# FEED_TIMER_DP_7.net
KiCad netlist of a schematic drawn in Altium Designer
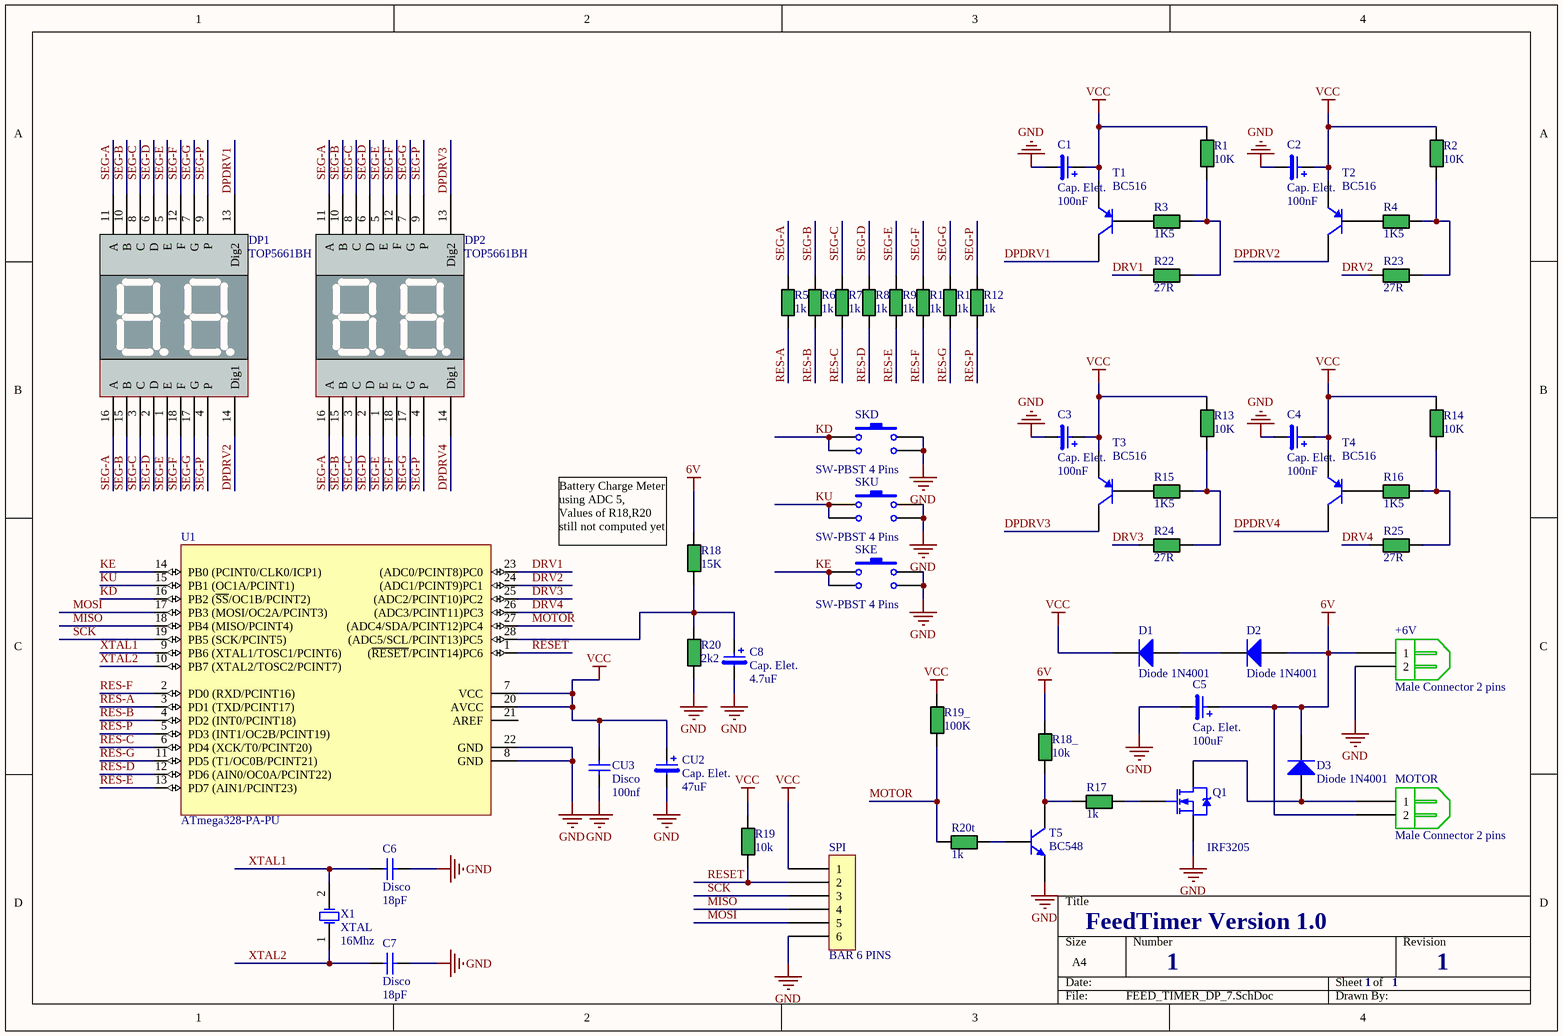
[diagram p0: FEED_TIMER_DP_7.SchDoc]

(export (version "E")
  (design (tool "Eeschema 10.0.6"))
  (components
    (comp (ref "+6V")
      (value "Male Connector 2 pins")
      (footprint "BR102A")
      (libsource (lib "NEPERMATH") (part "Male Con 2 Pin"))
    )
    (comp (ref "C1")
      (value "Cap. Elet.")
      (footprint "CAP ELE RAD 11mm H")
      (description "Capacitor Radial Eletrolitico")
      (fields (field (name "ALTIUM_VALUE") "100nF"))
      (libsource (lib "NEPERMATH") (part "CAP_RADIAL_ELETROLITICO"))
    )
    (comp (ref "C2")
      (value "Cap. Elet.")
      (footprint "CAP ELE RAD 11mm H")
      (description "Capacitor Radial Eletrolitico")
      (fields (field (name "ALTIUM_VALUE") "100nF"))
      (libsource (lib "NEPERMATH") (part "CAP_RADIAL_ELETROLITICO"))
    )
    (comp (ref "C3")
      (value "Cap. Elet.")
      (footprint "CAP ELE RAD 11mm H")
      (description "Capacitor Radial Eletrolitico")
      (fields (field (name "ALTIUM_VALUE") "100nF"))
      (libsource (lib "NEPERMATH") (part "CAP_RADIAL_ELETROLITICO"))
    )
    (comp (ref "C4")
      (value "Cap. Elet.")
      (footprint "CAP ELE RAD 11mm H")
      (description "Capacitor Radial Eletrolitico")
      (fields (field (name "ALTIUM_VALUE") "100nF"))
      (libsource (lib "NEPERMATH") (part "CAP_RADIAL_ELETROLITICO"))
    )
    (comp (ref "C5")
      (value "Cap. Elet.")
      (footprint "CAP_RADIAL_2_10_16")
      (description "Capacitor Radial Eletrolitico")
      (fields (field (name "ALTIUM_VALUE") "100uF"))
      (libsource (lib "NEPERMATH") (part "CAP_RADIAL_ELETROLITICO"))
    )
    (comp (ref "C6")
      (value "Disco")
      (footprint "CAP CER DISK 3MM")
      (description "SMD Capacitor 1210 size")
      (fields (field (name "ALTIUM_VALUE") "18pF"))
      (libsource (lib "NEPERMATH") (part "CAP_DISCO"))
    )
    (comp (ref "C7")
      (value "Disco")
      (footprint "CAP CER DISK 3MM")
      (description "SMD Capacitor 1210 size")
      (fields (field (name "ALTIUM_VALUE") "18pF"))
      (libsource (lib "NEPERMATH") (part "CAP_DISCO"))
    )
    (comp (ref "C8")
      (value "Cap. Elet.")
      (footprint "CAP ELE RAD 11mm H")
      (description "Capacitor Radial Eletrolitico")
      (fields (field (name "ALTIUM_VALUE") "4.7uF"))
      (libsource (lib "NEPERMATH") (part "CAP_RADIAL_ELETROLITICO"))
    )
    (comp (ref "CU2")
      (value "Cap. Elet.")
      (footprint "CAP ELE RAD 11mm H")
      (description "Capacitor Radial Eletrolitico")
      (fields (field (name "ALTIUM_VALUE") "47uF"))
      (libsource (lib "NEPERMATH") (part "CAP_RADIAL_ELETROLITICO"))
    )
    (comp (ref "CU3")
      (value "Disco")
      (footprint "CAP CER DISK 5MM")
      (description "SMD Capacitor 1210 size")
      (fields (field (name "ALTIUM_VALUE") "100nf"))
      (libsource (lib "NEPERMATH") (part "CAP_DISCO"))
    )
    (comp (ref "D1")
      (value "Diode 1N4001")
      (footprint "DO-41")
      (description "1 Amp General Purpose Rectifier")
      (fields (field (name "PUBLISHER") "Altium Limited"))
      (libsource (lib "NEPERMATH") (part "Diode 1N4001"))
    )
    (comp (ref "D2")
      (value "Diode 1N4001")
      (footprint "DO-41")
      (description "1 Amp General Purpose Rectifier")
      (fields (field (name "PUBLISHER") "Altium Limited"))
      (libsource (lib "NEPERMATH") (part "Diode 1N4001"))
    )
    (comp (ref "D3")
      (value "Diode 1N4001")
      (footprint "DO-41")
      (description "1 Amp General Purpose Rectifier")
      (fields (field (name "PUBLISHER") "Altium Limited"))
      (libsource (lib "NEPERMATH") (part "Diode 1N4001"))
    )
    (comp (ref "DP1")
      (value "TOP5661BH")
      (footprint "DISPLAY TOP_5261BH")
      (description "7 seg display")
      (libsource (lib "NEPERMATH") (part "DISPLAY TOP_5261BH"))
    )
    (comp (ref "DP2")
      (value "TOP5661BH")
      (footprint "DISPLAY TOP_5261BH")
      (description "7 seg display")
      (libsource (lib "NEPERMATH") (part "DISPLAY TOP_5261BH"))
    )
    (comp (ref "MOTOR")
      (value "Male Connector 2 pins")
      (footprint "BR102A")
      (libsource (lib "NEPERMATH") (part "Male Con 2 Pin"))
    )
    (comp (ref "Q1")
      (value "IRF3205")
      (footprint "KC03 - Deitado")
      (description "HEXFET Power MOSFET")
      (libsource (lib "NEPERMATH") (part "T-HEXFET N"))
    )
    (comp (ref "R1")
      (value "10K")
      (footprint "RES 300 CR25")
      (description "Generic Resistor")
      (fields (field (name "Comment") "Resistor Generic"))
      (libsource (lib "") (part "Resistor Generic_1"))
    )
    (comp (ref "R2")
      (value "10K")
      (footprint "RES 300 CR25")
      (description "Generic Resistor")
      (fields (field (name "Comment") "Resistor Generic"))
      (libsource (lib "") (part "Resistor Generic_1"))
    )
    (comp (ref "R3")
      (value "1K5")
      (footprint "RES 300 CR25")
      (description "Generic Resistor")
      (fields (field (name "Comment") "Resistor Generic"))
      (libsource (lib "NEPERMATH") (part "Resistor Generic"))
    )
    (comp (ref "R4")
      (value "1K5")
      (footprint "RES 300 CR25")
      (description "Generic Resistor")
      (fields (field (name "Comment") "Resistor Generic"))
      (libsource (lib "NEPERMATH") (part "Resistor Generic"))
    )
    (comp (ref "R5")
      (value "1k")
      (footprint "RES 300 CR25")
      (description "Generic Resistor")
      (fields (field (name "Comment") "Resistor Generic"))
      (libsource (lib "") (part "Resistor Generic_2"))
    )
    (comp (ref "R6")
      (value "1k")
      (footprint "RES 300 CR25")
      (description "Generic Resistor")
      (fields (field (name "Comment") "Resistor Generic"))
      (libsource (lib "") (part "Resistor Generic_2"))
    )
    (comp (ref "R7")
      (value "1k")
      (footprint "RES 300 CR25")
      (description "Generic Resistor")
      (fields (field (name "Comment") "Resistor Generic"))
      (libsource (lib "") (part "Resistor Generic_2"))
    )
    (comp (ref "R8")
      (value "1k")
      (footprint "RES 300 CR25")
      (description "Generic Resistor")
      (fields (field (name "Comment") "Resistor Generic"))
      (libsource (lib "") (part "Resistor Generic_2"))
    )
    (comp (ref "R9")
      (value "1k")
      (footprint "RES 300 CR25")
      (description "Generic Resistor")
      (fields (field (name "Comment") "Resistor Generic"))
      (libsource (lib "") (part "Resistor Generic_2"))
    )
    (comp (ref "R10")
      (value "1k")
      (footprint "RES 300 CR25")
      (description "Generic Resistor")
      (fields (field (name "Comment") "Resistor Generic"))
      (libsource (lib "") (part "Resistor Generic_2"))
    )
    (comp (ref "R11")
      (value "1k")
      (footprint "RES 300 CR25")
      (description "Generic Resistor")
      (fields (field (name "Comment") "Resistor Generic"))
      (libsource (lib "") (part "Resistor Generic_2"))
    )
    (comp (ref "R12")
      (value "1k")
      (footprint "RES 300 CR25")
      (description "Generic Resistor")
      (fields (field (name "Comment") "Resistor Generic"))
      (libsource (lib "") (part "Resistor Generic_2"))
    )
    (comp (ref "R13")
      (value "10K")
      (footprint "RES 300 CR25")
      (description "Generic Resistor")
      (fields (field (name "Comment") "Resistor Generic"))
      (libsource (lib "") (part "Resistor Generic_1"))
    )
    (comp (ref "R14")
      (value "10K")
      (footprint "RES 300 CR25")
      (description "Generic Resistor")
      (fields (field (name "Comment") "Resistor Generic"))
      (libsource (lib "") (part "Resistor Generic_1"))
    )
    (comp (ref "R15")
      (value "1K5")
      (footprint "RES 300 CR25")
      (description "Generic Resistor")
      (fields (field (name "Comment") "Resistor Generic"))
      (libsource (lib "NEPERMATH") (part "Resistor Generic"))
    )
    (comp (ref "R16")
      (value "1K5")
      (footprint "RES 300 CR25")
      (description "Generic Resistor")
      (fields (field (name "Comment") "Resistor Generic"))
      (libsource (lib "NEPERMATH") (part "Resistor Generic"))
    )
    (comp (ref "R17")
      (value "1k")
      (footprint "RES 300 CR25")
      (description "Generic Resistor")
      (fields (field (name "Comment") "Resistor Generic"))
      (libsource (lib "NEPERMATH") (part "Resistor Generic"))
    )
    (comp (ref "R18")
      (value "15K")
      (footprint "RES 300 CR25")
      (description "Generic Resistor")
      (fields (field (name "Comment") "Resistor Generic"))
      (libsource (lib "") (part "Resistor Generic_1"))
    )
    (comp (ref "R18_")
      (value "10k")
      (footprint "RES 300 CR25")
      (description "Generic Resistor")
      (fields (field (name "Comment") "Resistor Generic"))
      (libsource (lib "") (part "Resistor Generic_1"))
    )
    (comp (ref "R19")
      (value "10k")
      (footprint "RES 300 CR25")
      (description "Generic Resistor")
      (fields (field (name "Comment") "Resistor Generic"))
      (libsource (lib "") (part "Resistor Generic_1"))
    )
    (comp (ref "R19_")
      (value "100K")
      (footprint "RES 300 CR25")
      (description "Generic Resistor")
      (fields (field (name "Comment") "Resistor Generic"))
      (libsource (lib "") (part "Resistor Generic_1"))
    )
    (comp (ref "R20")
      (value "2k2")
      (footprint "RES 300 CR25")
      (description "Generic Resistor")
      (fields (field (name "Comment") "Resistor Generic"))
      (libsource (lib "") (part "Resistor Generic_1"))
    )
    (comp (ref "R20t")
      (value "1k")
      (footprint "RES 300 CR25")
      (description "Generic Resistor")
      (fields (field (name "Comment") "Resistor Generic"))
      (libsource (lib "NEPERMATH") (part "Resistor Generic"))
    )
    (comp (ref "R22")
      (value "27R")
      (footprint "RES 300 CR25")
      (description "Generic Resistor")
      (fields (field (name "Comment") "Resistor Generic"))
      (libsource (lib "NEPERMATH") (part "Resistor Generic"))
    )
    (comp (ref "R23")
      (value "27R")
      (footprint "RES 300 CR25")
      (description "Generic Resistor")
      (fields (field (name "Comment") "Resistor Generic"))
      (libsource (lib "NEPERMATH") (part "Resistor Generic"))
    )
    (comp (ref "R24")
      (value "27R")
      (footprint "RES 300 CR25")
      (description "Generic Resistor")
      (fields (field (name "Comment") "Resistor Generic"))
      (libsource (lib "NEPERMATH") (part "Resistor Generic"))
    )
    (comp (ref "R25")
      (value "27R")
      (footprint "RES 300 CR25")
      (description "Generic Resistor")
      (fields (field (name "Comment") "Resistor Generic"))
      (libsource (lib "NEPERMATH") (part "Resistor Generic"))
    )
    (comp (ref "SKD")
      (value "SW-PBST 4 Pins")
      (footprint "SW-PBST 4 Pins - SKHH 17 mm")
      (fields (field (name "PUBLISHER") "Altium Limited"))
      (libsource (lib "NEPERMATH") (part "SW-PBST 4 Pins SKHH"))
    )
    (comp (ref "SKE")
      (value "SW-PBST 4 Pins")
      (footprint "SW-PBST 4 Pins - SKHH 17 mm")
      (fields (field (name "PUBLISHER") "Altium Limited"))
      (libsource (lib "NEPERMATH") (part "SW-PBST 4 Pins SKHH"))
    )
    (comp (ref "SKU")
      (value "SW-PBST 4 Pins")
      (footprint "SW-PBST 4 Pins - SKHH 17 mm")
      (fields (field (name "PUBLISHER") "Altium Limited"))
      (libsource (lib "NEPERMATH") (part "SW-PBST 4 Pins SKHH"))
    )
    (comp (ref "SPI")
      (value "BAR 6 PINS")
      (footprint "HEADER BAR 6 PINS")
      (description ".100 Inch AMPMODU Headers 1-826629-0 (Tyco)")
      (libsource (lib "NEPERMATH") (part "HEADER BAR  6 PINS"))
    )
    (comp (ref "T1")
      (value "BC516")
      (footprint "TO-92 - Large")
      (description "General Bipolar Transistor NPN")
      (libsource (lib "NEPERMATH") (part "T-PNP"))
    )
    (comp (ref "T2")
      (value "BC516")
      (footprint "TO-92")
      (description "General Bipolar Transistor NPN")
      (libsource (lib "NEPERMATH") (part "T-PNP"))
    )
    (comp (ref "T3")
      (value "BC516")
      (footprint "TO-92")
      (description "General Bipolar Transistor NPN")
      (libsource (lib "NEPERMATH") (part "T-PNP"))
    )
    (comp (ref "T4")
      (value "BC516")
      (footprint "TO-92")
      (description "General Bipolar Transistor NPN")
      (libsource (lib "NEPERMATH") (part "T-PNP"))
    )
    (comp (ref "T5")
      (value "BC548")
      (footprint "TO-92 - BIG")
      (description "General Bipolar Transistor NPN")
      (fields (field (name "Comment") "Transistor"))
      (libsource (lib "NEPERMATH") (part "T-NPN"))
    )
    (comp (ref "U1")
      (value "ATmega328-PA-PU")
      (footprint "28P3")
      (description "8-Bit AVR Microcontroller with 8K Bytes of In-System Programmable Flash Memory")
      (libsource (lib "NEPERMATH") (part "ATmega328-PA-PU"))
    )
    (comp (ref "X1")
      (value "XTAL")
      (footprint "XTAL CILINDRIC DEITADO")
      (description "Crystal Oscillator")
      (fields (field (name "ALTIUM_VALUE") "16Mhz"))
      (libsource (lib "NEPERMATH") (part "XTAL"))
    )
  )
  (nets
    (net (code "1") (name "/DPDRV1") (class "Default")
      (node (ref "DP1") (pin "13") (pinfunction "Dig2_13") (pintype "passive"))
      (node (ref "T1") (pin "3") (pinfunction "C_3") (pintype "passive"))
    )
    (net (code "2") (name "/DPDRV2") (class "Default")
      (node (ref "DP1") (pin "14") (pinfunction "Dig1_14") (pintype "passive"))
      (node (ref "T2") (pin "3") (pinfunction "C_3") (pintype "passive"))
    )
    (net (code "3") (name "/DPDRV3") (class "Default")
      (node (ref "DP2") (pin "13") (pinfunction "Dig2_13") (pintype "passive"))
      (node (ref "T3") (pin "3") (pinfunction "C_3") (pintype "passive"))
    )
    (net (code "4") (name "/DPDRV4") (class "Default")
      (node (ref "DP2") (pin "14") (pinfunction "Dig1_14") (pintype "passive"))
      (node (ref "T4") (pin "3") (pinfunction "C_3") (pintype "passive"))
    )
    (net (code "5") (name "/DRV1") (class "Default")
      (node (ref "R22") (pin "1") (pinfunction "1_1") (pintype "passive"))
      (node (ref "U1") (pin "23") (pinfunction "(ADC0/PCINT8)PC0_23") (pintype "bidirectional"))
    )
    (net (code "6") (name "/DRV2") (class "Default")
      (node (ref "R23") (pin "1") (pinfunction "1_1") (pintype "passive"))
      (node (ref "U1") (pin "24") (pinfunction "(ADC1/PCINT9)PC1_24") (pintype "bidirectional"))
    )
    (net (code "7") (name "/DRV3") (class "Default")
      (node (ref "R24") (pin "1") (pinfunction "1_1") (pintype "passive"))
      (node (ref "U1") (pin "25") (pinfunction "(ADC2/PCINT10)PC2_25") (pintype "bidirectional"))
    )
    (net (code "8") (name "/DRV4") (class "Default")
      (node (ref "R25") (pin "1") (pinfunction "1_1") (pintype "passive"))
      (node (ref "U1") (pin "26") (pinfunction "(ADC3/PCINT11)PC3_26") (pintype "bidirectional"))
    )
    (net (code "9") (name "/KD") (class "Default")
      (node (ref "SKD") (pin "3") (pinfunction "3_3") (pintype "passive"))
      (node (ref "SKD") (pin "4") (pinfunction "4_4") (pintype "passive"))
      (node (ref "U1") (pin "16") (pinfunction "PB2_(~{SS}/OC1B/PCINT2)_16") (pintype "bidirectional"))
    )
    (net (code "10") (name "/KE") (class "Default")
      (node (ref "SKE") (pin "3") (pinfunction "3_3") (pintype "passive"))
      (node (ref "SKE") (pin "4") (pinfunction "4_4") (pintype "passive"))
      (node (ref "U1") (pin "14") (pinfunction "PB0_(PCINT0/CLK0/ICP1)_14") (pintype "bidirectional"))
    )
    (net (code "11") (name "/KU") (class "Default")
      (node (ref "SKU") (pin "3") (pinfunction "3_3") (pintype "passive"))
      (node (ref "SKU") (pin "4") (pinfunction "4_4") (pintype "passive"))
      (node (ref "U1") (pin "15") (pinfunction "PB1_(OC1A/PCINT1)_15") (pintype "bidirectional"))
    )
    (net (code "12") (name "/MISO") (class "Default")
      (node (ref "SPI") (pin "4") (pinfunction "4_4") (pintype "passive"))
      (node (ref "U1") (pin "18") (pinfunction "PB4_(MISO/PCINT4)_18") (pintype "bidirectional"))
    )
    (net (code "13") (name "/MOSI") (class "Default")
      (node (ref "SPI") (pin "5") (pinfunction "5_5") (pintype "passive"))
      (node (ref "U1") (pin "17") (pinfunction "PB3_(MOSI/OC2A/PCINT3)_17") (pintype "bidirectional"))
    )
    (net (code "14") (name "/MOTOR") (class "Default")
      (node (ref "R19_") (pin "1") (pinfunction "1_1") (pintype "passive"))
      (node (ref "R20t") (pin "1") (pinfunction "1_1") (pintype "passive"))
      (node (ref "U1") (pin "27") (pinfunction "(ADC4/SDA/PCINT12)PC4_27") (pintype "bidirectional"))
    )
    (net (code "15") (name "/RES-A") (class "Default")
      (node (ref "R5") (pin "2") (pinfunction "2_2") (pintype "passive"))
      (node (ref "U1") (pin "3") (pinfunction "PD1_(TXD/PCINT17)_3") (pintype "bidirectional"))
    )
    (net (code "16") (name "/RES-B") (class "Default")
      (node (ref "R6") (pin "2") (pinfunction "2_2") (pintype "passive"))
      (node (ref "U1") (pin "4") (pinfunction "PD2_(INT0/PCINT18)_4") (pintype "bidirectional"))
    )
    (net (code "17") (name "/RES-C") (class "Default")
      (node (ref "R7") (pin "2") (pinfunction "2_2") (pintype "passive"))
      (node (ref "U1") (pin "6") (pinfunction "PD4_(XCK/T0/PCINT20)_6") (pintype "bidirectional"))
    )
    (net (code "18") (name "/RES-D") (class "Default")
      (node (ref "R8") (pin "2") (pinfunction "2_2") (pintype "passive"))
      (node (ref "U1") (pin "12") (pinfunction "PD6_(AIN0/OC0A/PCINT22)_12") (pintype "bidirectional"))
    )
    (net (code "19") (name "/RES-E") (class "Default")
      (node (ref "R9") (pin "2") (pinfunction "2_2") (pintype "passive"))
      (node (ref "U1") (pin "13") (pinfunction "PD7_(AIN1/PCINT23)_13") (pintype "bidirectional"))
    )
    (net (code "20") (name "/RES-F") (class "Default")
      (node (ref "R10") (pin "2") (pinfunction "2_2") (pintype "passive"))
      (node (ref "U1") (pin "2") (pinfunction "PD0_(RXD/PCINT16)_2") (pintype "bidirectional"))
    )
    (net (code "21") (name "/RES-G") (class "Default")
      (node (ref "R11") (pin "2") (pinfunction "2_2") (pintype "passive"))
      (node (ref "U1") (pin "11") (pinfunction "PD5_(T1/OC0B/PCINT21)_11") (pintype "bidirectional"))
    )
    (net (code "22") (name "/RES-P") (class "Default")
      (node (ref "R12") (pin "2") (pinfunction "2_2") (pintype "passive"))
      (node (ref "U1") (pin "5") (pinfunction "PD3_(INT1/OC2B/PCINT19)_5") (pintype "bidirectional"))
    )
    (net (code "23") (name "/RESET") (class "Default")
      (node (ref "R19") (pin "1") (pinfunction "1_1") (pintype "passive"))
      (node (ref "SPI") (pin "2") (pinfunction "2_2") (pintype "passive"))
      (node (ref "U1") (pin "1") (pinfunction "(~{RESET}/PCINT14)PC6_1") (pintype "bidirectional"))
    )
    (net (code "24") (name "/SCK") (class "Default")
      (node (ref "SPI") (pin "3") (pinfunction "3_3") (pintype "passive"))
      (node (ref "U1") (pin "19") (pinfunction "PB5_(SCK/PCINT5)_19") (pintype "bidirectional"))
    )
    (net (code "25") (name "/SEG-A") (class "Default")
      (node (ref "DP1") (pin "11") (pinfunction "A_11") (pintype "passive"))
      (node (ref "DP1") (pin "16") (pinfunction "A_16") (pintype "passive"))
      (node (ref "DP2") (pin "11") (pinfunction "A_11") (pintype "passive"))
      (node (ref "DP2") (pin "16") (pinfunction "A_16") (pintype "passive"))
      (node (ref "R5") (pin "1") (pinfunction "1_1") (pintype "passive"))
    )
    (net (code "26") (name "/SEG-B") (class "Default")
      (node (ref "DP1") (pin "10") (pinfunction "B_10") (pintype "passive"))
      (node (ref "DP1") (pin "15") (pinfunction "B_15") (pintype "passive"))
      (node (ref "DP2") (pin "10") (pinfunction "B_10") (pintype "passive"))
      (node (ref "DP2") (pin "15") (pinfunction "B_15") (pintype "passive"))
      (node (ref "R6") (pin "1") (pinfunction "1_1") (pintype "passive"))
    )
    (net (code "27") (name "/SEG-C") (class "Default")
      (node (ref "DP1") (pin "3") (pinfunction "C_3") (pintype "passive"))
      (node (ref "DP1") (pin "8") (pinfunction "C_8") (pintype "passive"))
      (node (ref "DP2") (pin "3") (pinfunction "C_3") (pintype "passive"))
      (node (ref "DP2") (pin "8") (pinfunction "C_8") (pintype "passive"))
      (node (ref "R7") (pin "1") (pinfunction "1_1") (pintype "passive"))
    )
    (net (code "28") (name "/SEG-D") (class "Default")
      (node (ref "DP1") (pin "2") (pinfunction "D_2") (pintype "passive"))
      (node (ref "DP1") (pin "6") (pinfunction "D_6") (pintype "passive"))
      (node (ref "DP2") (pin "2") (pinfunction "D_2") (pintype "passive"))
      (node (ref "DP2") (pin "6") (pinfunction "D_6") (pintype "passive"))
      (node (ref "R8") (pin "1") (pinfunction "1_1") (pintype "passive"))
    )
    (net (code "29") (name "/SEG-E") (class "Default")
      (node (ref "DP1") (pin "1") (pinfunction "E_1") (pintype "passive"))
      (node (ref "DP1") (pin "5") (pinfunction "E_5") (pintype "passive"))
      (node (ref "DP2") (pin "1") (pinfunction "E_1") (pintype "passive"))
      (node (ref "DP2") (pin "5") (pinfunction "E_5") (pintype "passive"))
      (node (ref "R9") (pin "1") (pinfunction "1_1") (pintype "passive"))
    )
    (net (code "30") (name "/SEG-F") (class "Default")
      (node (ref "DP1") (pin "12") (pinfunction "F_12") (pintype "passive"))
      (node (ref "DP1") (pin "18") (pinfunction "F_18") (pintype "passive"))
      (node (ref "DP2") (pin "12") (pinfunction "F_12") (pintype "passive"))
      (node (ref "DP2") (pin "18") (pinfunction "F_18") (pintype "passive"))
      (node (ref "R10") (pin "1") (pinfunction "1_1") (pintype "passive"))
    )
    (net (code "31") (name "/SEG-G") (class "Default")
      (node (ref "DP1") (pin "17") (pinfunction "G_17") (pintype "passive"))
      (node (ref "DP1") (pin "7") (pinfunction "G_7") (pintype "passive"))
      (node (ref "DP2") (pin "17") (pinfunction "G_17") (pintype "passive"))
      (node (ref "DP2") (pin "7") (pinfunction "G_7") (pintype "passive"))
      (node (ref "R11") (pin "1") (pinfunction "1_1") (pintype "passive"))
    )
    (net (code "32") (name "/SEG-P") (class "Default")
      (node (ref "DP1") (pin "4") (pinfunction "P_4") (pintype "passive"))
      (node (ref "DP1") (pin "9") (pinfunction "P_9") (pintype "passive"))
      (node (ref "DP2") (pin "4") (pinfunction "P_4") (pintype "passive"))
      (node (ref "DP2") (pin "9") (pinfunction "P_9") (pintype "passive"))
      (node (ref "R12") (pin "1") (pinfunction "1_1") (pintype "passive"))
    )
    (net (code "33") (name "/XTAL1") (class "Default")
      (node (ref "C6") (pin "1") (pinfunction "1_1") (pintype "passive"))
      (node (ref "U1") (pin "9") (pinfunction "PB6_(XTAL1/TOSC1/PCINT6)_9") (pintype "bidirectional"))
      (node (ref "X1") (pin "2") (pinfunction "OSC2_2") (pintype "passive"))
    )
    (net (code "34") (name "/XTAL2") (class "Default")
      (node (ref "C7") (pin "1") (pinfunction "1_1") (pintype "passive"))
      (node (ref "U1") (pin "10") (pinfunction "PB7_(XTAL2/TOSC2/PCINT7)_10") (pintype "bidirectional"))
      (node (ref "X1") (pin "1") (pinfunction "OSC1_1") (pintype "passive"))
    )
    (net (code "35") (name "6V") (class "Default")
      (node (ref "+6V") (pin "1") (pinfunction "1_1") (pintype "passive"))
      (node (ref "C5") (pin "1") (pinfunction "1_1") (pintype "passive"))
      (node (ref "D2") (pin "1") (pinfunction "A_1") (pintype "passive"))
      (node (ref "D3") (pin "2") (pinfunction "K_2") (pintype "passive"))
      (node (ref "MOTOR") (pin "2") (pinfunction "2_2") (pintype "passive"))
      (node (ref "R18") (pin "2") (pinfunction "2_2") (pintype "passive"))
      (node (ref "R18_") (pin "2") (pinfunction "2_2") (pintype "passive"))
    )
    (net (code "36") (name "GND") (class "Default")
      (node (ref "+6V") (pin "2") (pinfunction "2_2") (pintype "passive"))
      (node (ref "C1") (pin "2") (pinfunction "2_2") (pintype "passive"))
      (node (ref "C2") (pin "2") (pinfunction "2_2") (pintype "passive"))
      (node (ref "C3") (pin "2") (pinfunction "2_2") (pintype "passive"))
      (node (ref "C4") (pin "2") (pinfunction "2_2") (pintype "passive"))
      (node (ref "C5") (pin "2") (pinfunction "2_2") (pintype "passive"))
      (node (ref "C6") (pin "2") (pinfunction "2_2") (pintype "passive"))
      (node (ref "C7") (pin "2") (pinfunction "2_2") (pintype "passive"))
      (node (ref "C8") (pin "2") (pinfunction "2_2") (pintype "passive"))
      (node (ref "CU2") (pin "2") (pinfunction "2_2") (pintype "passive"))
      (node (ref "CU3") (pin "2") (pinfunction "2_2") (pintype "passive"))
      (node (ref "Q1") (pin "3") (pinfunction "S_3") (pintype "passive"))
      (node (ref "R20") (pin "1") (pinfunction "1_1") (pintype "passive"))
      (node (ref "SKD") (pin "1") (pinfunction "1_1") (pintype "passive"))
      (node (ref "SKD") (pin "2") (pinfunction "2_2") (pintype "passive"))
      (node (ref "SKE") (pin "1") (pinfunction "1_1") (pintype "passive"))
      (node (ref "SKE") (pin "2") (pinfunction "2_2") (pintype "passive"))
      (node (ref "SKU") (pin "1") (pinfunction "1_1") (pintype "passive"))
      (node (ref "SKU") (pin "2") (pinfunction "2_2") (pintype "passive"))
      (node (ref "SPI") (pin "6") (pinfunction "6_6") (pintype "passive"))
      (node (ref "T5") (pin "1") (pinfunction "E_1") (pintype "passive"))
      (node (ref "U1") (pin "22") (pinfunction "GND_22") (pintype "power_in"))
      (node (ref "U1") (pin "8") (pinfunction "GND_8") (pintype "power_in"))
    )
    (net (code "37") (name "Net-(D1-A)") (class "Default")
      (node (ref "D1") (pin "1") (pinfunction "A_1") (pintype "passive"))
      (node (ref "D2") (pin "2") (pinfunction "K_2") (pintype "passive"))
    )
    (net (code "38") (name "Net-(D3-A)") (class "Default")
      (node (ref "D3") (pin "1") (pinfunction "A_1") (pintype "passive"))
      (node (ref "MOTOR") (pin "1") (pinfunction "1_1") (pintype "passive"))
      (node (ref "Q1") (pin "2") (pinfunction "D_2") (pintype "passive"))
    )
    (net (code "39") (name "Net-(Q1-G)") (class "Default")
      (node (ref "Q1") (pin "1") (pinfunction "G_1") (pintype "passive"))
      (node (ref "R17") (pin "2") (pinfunction "2_2") (pintype "passive"))
    )
    (net (code "40") (name "Net-(R1-Pad1)") (class "Default")
      (node (ref "R1") (pin "1") (pinfunction "1_1") (pintype "passive"))
      (node (ref "R22") (pin "2") (pinfunction "2_2") (pintype "passive"))
      (node (ref "R3") (pin "2") (pinfunction "2_2") (pintype "passive"))
    )
    (net (code "41") (name "Net-(R2-Pad1)") (class "Default")
      (node (ref "R2") (pin "1") (pinfunction "1_1") (pintype "passive"))
      (node (ref "R23") (pin "2") (pinfunction "2_2") (pintype "passive"))
      (node (ref "R4") (pin "2") (pinfunction "2_2") (pintype "passive"))
    )
    (net (code "42") (name "Net-(R13-Pad1)") (class "Default")
      (node (ref "R13") (pin "1") (pinfunction "1_1") (pintype "passive"))
      (node (ref "R15") (pin "2") (pinfunction "2_2") (pintype "passive"))
      (node (ref "R24") (pin "2") (pinfunction "2_2") (pintype "passive"))
    )
    (net (code "43") (name "Net-(R14-Pad1)") (class "Default")
      (node (ref "R14") (pin "1") (pinfunction "1_1") (pintype "passive"))
      (node (ref "R16") (pin "2") (pinfunction "2_2") (pintype "passive"))
      (node (ref "R25") (pin "2") (pinfunction "2_2") (pintype "passive"))
    )
    (net (code "44") (name "Net-(T1-B)") (class "Default")
      (node (ref "R3") (pin "1") (pinfunction "1_1") (pintype "passive"))
      (node (ref "T1") (pin "2") (pinfunction "B_2") (pintype "passive"))
    )
    (net (code "45") (name "Net-(T2-B)") (class "Default")
      (node (ref "R4") (pin "1") (pinfunction "1_1") (pintype "passive"))
      (node (ref "T2") (pin "2") (pinfunction "B_2") (pintype "passive"))
    )
    (net (code "46") (name "Net-(T3-B)") (class "Default")
      (node (ref "R15") (pin "1") (pinfunction "1_1") (pintype "passive"))
      (node (ref "T3") (pin "2") (pinfunction "B_2") (pintype "passive"))
    )
    (net (code "47") (name "Net-(T4-B)") (class "Default")
      (node (ref "R16") (pin "1") (pinfunction "1_1") (pintype "passive"))
      (node (ref "T4") (pin "2") (pinfunction "B_2") (pintype "passive"))
    )
    (net (code "48") (name "Net-(T5-B)") (class "Default")
      (node (ref "R20t") (pin "2") (pinfunction "2_2") (pintype "passive"))
      (node (ref "T5") (pin "2") (pinfunction "B_2") (pintype "passive"))
    )
    (net (code "49") (name "Net-(T5-C)") (class "Default")
      (node (ref "R17") (pin "1") (pinfunction "1_1") (pintype "passive"))
      (node (ref "R18_") (pin "1") (pinfunction "1_1") (pintype "passive"))
      (node (ref "T5") (pin "3") (pinfunction "C_3") (pintype "passive"))
    )
    (net (code "50") (name "Net-(U1-(ADC5{slash}SCL{slash}PCINT13)PC5)") (class "Default")
      (node (ref "C8") (pin "1") (pinfunction "1_1") (pintype "passive"))
      (node (ref "R18") (pin "1") (pinfunction "1_1") (pintype "passive"))
      (node (ref "R20") (pin "2") (pinfunction "2_2") (pintype "passive"))
      (node (ref "U1") (pin "28") (pinfunction "(ADC5/SCL/PCINT13)PC5_28") (pintype "bidirectional"))
    )
    (net (code "51") (name "VCC") (class "Default")
      (node (ref "C1") (pin "1") (pinfunction "1_1") (pintype "passive"))
      (node (ref "C2") (pin "1") (pinfunction "1_1") (pintype "passive"))
      (node (ref "C3") (pin "1") (pinfunction "1_1") (pintype "passive"))
      (node (ref "C4") (pin "1") (pinfunction "1_1") (pintype "passive"))
      (node (ref "CU2") (pin "1") (pinfunction "1_1") (pintype "passive"))
      (node (ref "CU3") (pin "1") (pinfunction "1_1") (pintype "passive"))
      (node (ref "D1") (pin "2") (pinfunction "K_2") (pintype "passive"))
      (node (ref "R1") (pin "2") (pinfunction "2_2") (pintype "passive"))
      (node (ref "R13") (pin "2") (pinfunction "2_2") (pintype "passive"))
      (node (ref "R14") (pin "2") (pinfunction "2_2") (pintype "passive"))
      (node (ref "R19") (pin "2") (pinfunction "2_2") (pintype "passive"))
      (node (ref "R19_") (pin "2") (pinfunction "2_2") (pintype "passive"))
      (node (ref "R2") (pin "2") (pinfunction "2_2") (pintype "passive"))
      (node (ref "SPI") (pin "1") (pinfunction "1_1") (pintype "passive"))
      (node (ref "T1") (pin "1") (pinfunction "E_1") (pintype "passive"))
      (node (ref "T2") (pin "1") (pinfunction "E_1") (pintype "passive"))
      (node (ref "T3") (pin "1") (pinfunction "E_1") (pintype "passive"))
      (node (ref "T4") (pin "1") (pinfunction "E_1") (pintype "passive"))
      (node (ref "U1") (pin "20") (pinfunction "AVCC_20") (pintype "power_in"))
      (node (ref "U1") (pin "7") (pinfunction "VCC_7") (pintype "power_in"))
    )
    (net (code "52") (name "unconnected-(U1-AREF-Pad21)") (class "Default")
      (node (ref "U1") (pin "21") (pinfunction "AREF_21") (pintype "passive"))
    )
  )
)
